# arduino_Uno_ref.net
KiCad netlist of a schematic drawn in EAGLE
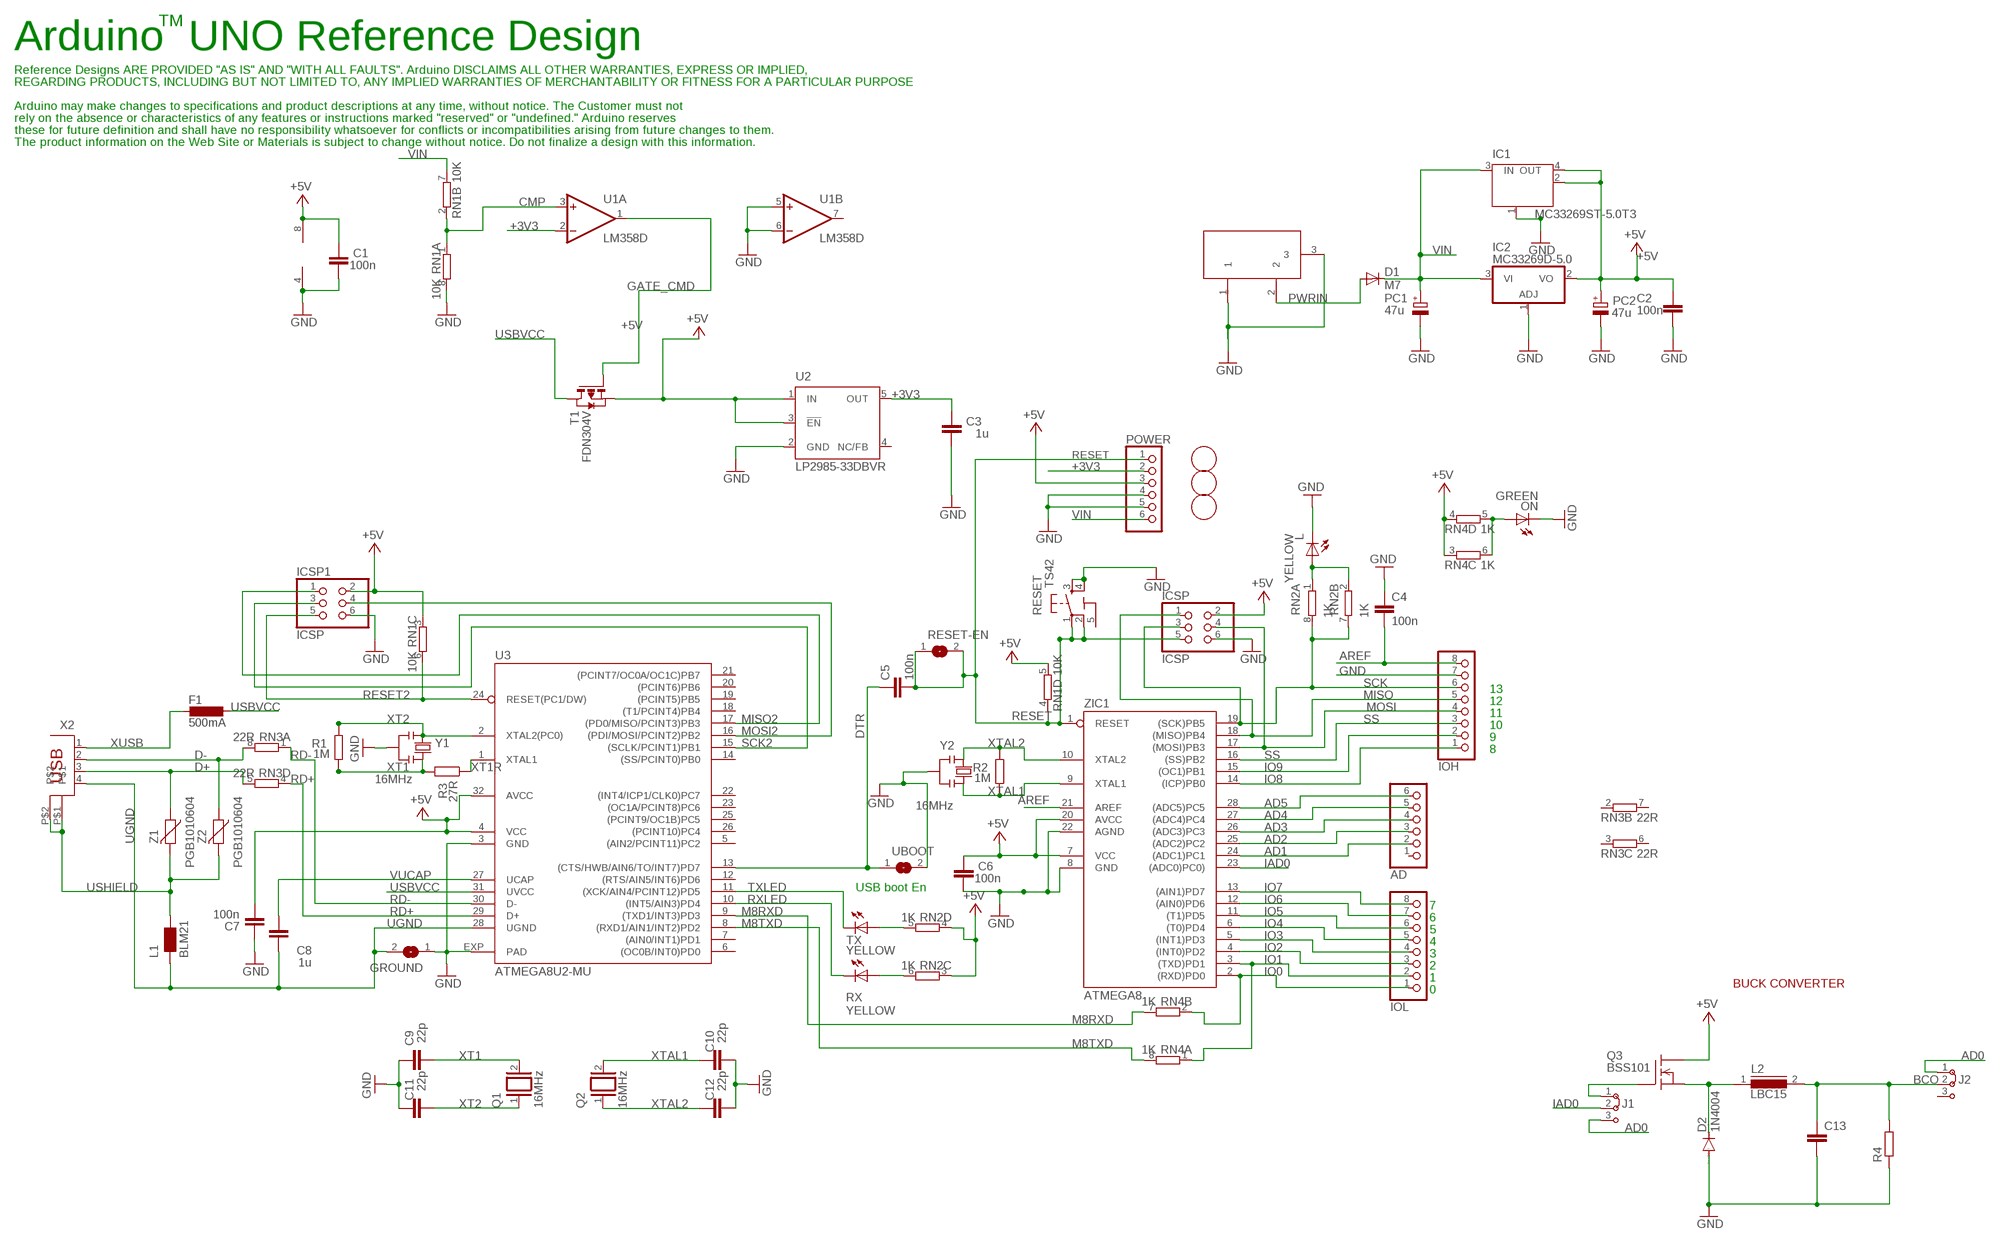
[diagram p0: schematic, sheet 1]

(export (version "E")
  (design (tool "Eeschema 10.0.6"))
  (components
    (comp (ref "AD")
      (value "PINHD-1X6")
      (footprint "eagle-import:1X06")
      (libsource (lib "eagle-import") (part "PINHD-1X6"))
    )
    (comp (ref "C1")
      (value "100n")
      (footprint "eagle-import:C0603-ROUND")
      (libsource (lib "eagle-import") (part "C-EU0603-RND"))
    )
    (comp (ref "C2")
      (value "100n")
      (footprint "eagle-import:C0603-ROUND")
      (libsource (lib "eagle-import") (part "C-EU0603-RND"))
    )
    (comp (ref "C3")
      (value "1u")
      (footprint "eagle-import:C0603-ROUND")
      (libsource (lib "eagle-import") (part "C-EU0603-RND"))
    )
    (comp (ref "C4")
      (value "100n")
      (footprint "eagle-import:C0603-ROUND")
      (libsource (lib "eagle-import") (part "C-EU0603-RND"))
    )
    (comp (ref "C5")
      (value "100n")
      (footprint "eagle-import:C0603-ROUND")
      (libsource (lib "eagle-import") (part "C-EU0603-RND"))
    )
    (comp (ref "C6")
      (value "100n")
      (footprint "eagle-import:C0603-ROUND")
      (libsource (lib "eagle-import") (part "C-EU0603-RND"))
    )
    (comp (ref "C7")
      (value "100n")
      (footprint "eagle-import:C0603-ROUND")
      (libsource (lib "eagle-import") (part "C-EU0603-RND"))
    )
    (comp (ref "C8")
      (value "1u")
      (footprint "eagle-import:C0603-ROUND")
      (libsource (lib "eagle-import") (part "C-EU0603-RND"))
    )
    (comp (ref "C9")
      (value "22p")
      (footprint "eagle-import:C0603-ROUND")
      (libsource (lib "eagle-import") (part "C-EU0603-RND"))
    )
    (comp (ref "C10")
      (value "22p")
      (footprint "eagle-import:C0603-ROUND")
      (libsource (lib "eagle-import") (part "C-EU0603-RND"))
    )
    (comp (ref "C11")
      (value "22p")
      (footprint "eagle-import:C0603-ROUND")
      (libsource (lib "eagle-import") (part "C-EU0603-RND"))
    )
    (comp (ref "C12")
      (value "22p")
      (footprint "eagle-import:C0603-ROUND")
      (libsource (lib "eagle-import") (part "C-EU0603-RND"))
    )
    (comp (ref "C13")
      (value "C2.5/2")
      (footprint "eagle-import:C2.5-2")
      (libsource (lib "eagle-import") (part "C2.5/2"))
    )
    (comp (ref "D1")
      (value "M7")
      (footprint "eagle-import:SMB")
      (libsource (lib "eagle-import") (part "DIODE-SMB"))
    )
    (comp (ref "D2")
      (value "1N4004")
      (footprint "eagle-import:DO41-10")
      (libsource (lib "eagle-import") (part "1N4004"))
    )
    (comp (ref "F1")
      (value "500mA")
      (footprint "eagle-import:L1812")
      (libsource (lib "eagle-import") (part "L-EUL1812"))
    )
    (comp (ref "GROUND")
      (value "SJ")
      (footprint "eagle-import:SJ")
      (libsource (lib "eagle-import") (part "SJ"))
    )
    (comp (ref "IC1")
      (value "MC33269ST-5.0T3")
      (footprint "eagle-import:SOT223")
      (libsource (lib "eagle-import") (part "MC33269ST-3.3T3"))
    )
    (comp (ref "IC2")
      (value "MC33269D-5.0")
      (footprint "eagle-import:DPACK")
      (libsource (lib "eagle-import") (part "MC33269?D-5.0"))
    )
    (comp (ref "ICSP")
      (value "ICSP")
      (footprint "eagle-import:2X03")
      (libsource (lib "eagle-import") (part "PINHD-2X3"))
    )
    (comp (ref "ICSP1")
      (value "ICSP")
      (footprint "eagle-import:2X03")
      (libsource (lib "eagle-import") (part "PINHD-2X3"))
    )
    (comp (ref "IOH")
      (value "PINHD-1X8")
      (footprint "eagle-import:1X08")
      (libsource (lib "eagle-import") (part "PINHD-1X8"))
    )
    (comp (ref "IOL")
      (value "PINHD-1X8")
      (footprint "eagle-import:1X08")
      (libsource (lib "eagle-import") (part "PINHD-1X8"))
    )
    (comp (ref "J1")
      (value "J2X2MM")
      (footprint "eagle-import:04C")
      (libsource (lib "eagle-import") (part "J2X2MM"))
    )
    (comp (ref "J2")
      (value "J2X2MM")
      (footprint "eagle-import:04C")
      (libsource (lib "eagle-import") (part "J2X2MM"))
    )
    (comp (ref "L")
      (value "YELLOW")
      (footprint "eagle-import:CHIP-LED0805")
      (libsource (lib "eagle-import") (part "LEDCHIP-LED0805"))
    )
    (comp (ref "L1")
      (value "BLM21")
      (footprint "eagle-import:0805")
      (libsource (lib "eagle-import") (part "WE-CBF_0805"))
    )
    (comp (ref "L2")
      (value "LBC15")
      (footprint "eagle-import:LBC15")
      (libsource (lib "eagle-import") (part "LBC15"))
    )
    (comp (ref "ON")
      (value "GREEN")
      (footprint "eagle-import:CHIP-LED0805")
      (libsource (lib "eagle-import") (part "LEDCHIP-LED0805"))
    )
    (comp (ref "PC1")
      (value "47u")
      (footprint "eagle-import:PANASONIC_D")
      (libsource (lib "eagle-import") (part "CPOL-EUD"))
    )
    (comp (ref "PC2")
      (value "47u")
      (footprint "eagle-import:PANASONIC_D")
      (libsource (lib "eagle-import") (part "CPOL-EUD"))
    )
    (comp (ref "POWER")
      (value "PINHD-1X6")
      (footprint "eagle-import:1X06")
      (libsource (lib "eagle-import") (part "PINHD-1X6"))
    )
    (comp (ref "Q1")
      (value "16MHz")
      (footprint "eagle-import:QS")
      (libsource (lib "eagle-import") (part "XTAL/S"))
    )
    (comp (ref "Q2")
      (value "16MHz")
      (footprint "eagle-import:QS")
      (libsource (lib "eagle-import") (part "XTAL/S"))
    )
    (comp (ref "Q3")
      (value "BSS101")
      (footprint "eagle-import:TO92")
      (libsource (lib "eagle-import") (part "BSS101"))
    )
    (comp (ref "R1")
      (value "1M")
      (footprint "eagle-import:R0603-ROUND")
      (libsource (lib "eagle-import") (part "R-EU_R0603"))
    )
    (comp (ref "R2")
      (value "1M")
      (footprint "eagle-import:R0603-ROUND")
      (libsource (lib "eagle-import") (part "R-EU_R0603"))
    )
    (comp (ref "R3")
      (value "27R")
      (footprint "eagle-import:R0603-ROUND")
      (libsource (lib "eagle-import") (part "R-EU_R0603"))
    )
    (comp (ref "R4")
      (value "R-EU_0207/10")
      (footprint "eagle-import:0207_10")
      (libsource (lib "eagle-import") (part "rcl_334_R-EU_0207/10"))
    )
    (comp (ref "RESET")
      (value "TS42")
      (footprint "eagle-import:TS42")
      (libsource (lib "eagle-import") (part "TS42"))
    )
    (comp (ref "RESET-EN")
      (value "SJ")
      (footprint "eagle-import:SJ")
      (libsource (lib "eagle-import") (part "SJ"))
    )
    (comp (ref "RN1")
      (value "10K")
      (footprint "eagle-import:CAY16")
      (libsource (lib "eagle-import") (part "4R-NCAY16"))
    )
    (comp (ref "RN2")
      (value "1K")
      (footprint "eagle-import:CAY16")
      (libsource (lib "eagle-import") (part "4R-NCAY16"))
    )
    (comp (ref "RN3")
      (value "22R")
      (footprint "eagle-import:CAY16")
      (libsource (lib "eagle-import") (part "4R-NCAY16"))
    )
    (comp (ref "RN4")
      (value "1K")
      (footprint "eagle-import:CAY16")
      (libsource (lib "eagle-import") (part "4R-NCAY16"))
    )
    (comp (ref "RX")
      (value "YELLOW")
      (footprint "eagle-import:CHIP-LED0805")
      (libsource (lib "eagle-import") (part "LEDCHIP-LED0805"))
    )
    (comp (ref "T1")
      (value "FDN304V")
      (footprint "eagle-import:SOT-23")
      (libsource (lib "eagle-import") (part "PMOSSOT23"))
    )
    (comp (ref "TX")
      (value "YELLOW")
      (footprint "eagle-import:CHIP-LED0805")
      (libsource (lib "eagle-import") (part "LEDCHIP-LED0805"))
    )
    (comp (ref "U$3")
      (value "FIDUCIALMOUNT")
      (footprint "eagle-import:FIDUCIA-MOUNT")
      (libsource (lib "eagle-import") (part "FIDUCIALMOUNT"))
    )
    (comp (ref "U$4")
      (value "FIDUCIALMOUNT")
      (footprint "eagle-import:FIDUCIA-MOUNT")
      (libsource (lib "eagle-import") (part "FIDUCIALMOUNT"))
    )
    (comp (ref "U$6")
      (value "FIDUCIALMOUNT")
      (footprint "eagle-import:FIDUCIA-MOUNT")
      (libsource (lib "eagle-import") (part "FIDUCIALMOUNT"))
    )
    (comp (ref "U1")
      (value "LM358D")
      (footprint "eagle-import:SO08")
      (libsource (lib "eagle-import") (part "LM358D"))
    )
    (comp (ref "U2")
      (value "LP2985-33DBVR")
      (footprint "eagle-import:SOT23-DBV")
      (libsource (lib "eagle-import") (part "TPS77033"))
    )
    (comp (ref "U3")
      (value "ATMEGA8U2-MU")
      (footprint "eagle-import:QFN32")
      (libsource (lib "eagle-import") (part "ATMEGA8U2-MU"))
    )
    (comp (ref "UBOOT")
      (value "SJ")
      (footprint "eagle-import:SJ")
      (libsource (lib "eagle-import") (part "SJ"))
    )
    (comp (ref "X1")
      (value "DC21MMX")
      (footprint "eagle-import:DC-21MM")
      (libsource (lib "eagle-import") (part "DC21MMX"))
    )
    (comp (ref "X2")
      (value "PN61729")
      (footprint "eagle-import:PN61729")
      (libsource (lib "eagle-import") (part "PN61729"))
    )
    (comp (ref "Y1")
      (value "16MHz")
      (footprint "eagle-import:RESONATOR")
      (libsource (lib "eagle-import") (part "RESONATORMU"))
    )
    (comp (ref "Y2")
      (value "16MHz")
      (footprint "eagle-import:RESONATOR")
      (libsource (lib "eagle-import") (part "RESONATORMU"))
    )
    (comp (ref "Z1")
      (value "PGB1010604")
      (footprint "eagle-import:CT_CN0603")
      (libsource (lib "eagle-import") (part "VARISTORCN0603"))
    )
    (comp (ref "Z2")
      (value "PGB1010604")
      (footprint "eagle-import:CT_CN0603")
      (libsource (lib "eagle-import") (part "VARISTORCN0603"))
    )
    (comp (ref "ZIC1")
      (value "ATMEGA8")
      (footprint "eagle-import:DIL28-3")
      (libsource (lib "eagle-import") (part "AT90S4433P"))
    )
  )
  (nets
    (net (code "1") (name "+5V") (class "Default")
      (node (ref "C1") (pin "2") (pinfunction "2_2") (pintype "passive"))
      (node (ref "C2") (pin "2") (pinfunction "2_2") (pintype "passive"))
      (node (ref "C6") (pin "2") (pinfunction "2_2") (pintype "passive"))
      (node (ref "C7") (pin "1") (pinfunction "1_1") (pintype "passive"))
      (node (ref "IC1") (pin "2") (pinfunction "OUT_2") (pintype "passive"))
      (node (ref "IC1") (pin "4") (pinfunction "OUT_4") (pintype "passive"))
      (node (ref "IC2") (pin "2") (pinfunction "VO_2") (pintype "passive"))
      (node (ref "ICSP") (pin "2") (pinfunction "2_2") (pintype "passive"))
      (node (ref "ICSP1") (pin "2") (pinfunction "2_2") (pintype "passive"))
      (node (ref "PC2") (pin "+") (pinfunction "+_+") (pintype "passive"))
      (node (ref "POWER") (pin "3") (pinfunction "3_3") (pintype "passive"))
      (node (ref "Q3") (pin "3") (pinfunction "D_3") (pintype "passive"))
      (node (ref "RN1") (pin "3") (pinfunction "1_3") (pintype "passive"))
      (node (ref "RN1") (pin "5") (pinfunction "2_5") (pintype "passive"))
      (node (ref "RN2") (pin "3") (pinfunction "1_3") (pintype "passive"))
      (node (ref "RN2") (pin "4") (pinfunction "1_4") (pintype "passive"))
      (node (ref "RN4") (pin "3") (pinfunction "1_3") (pintype "passive"))
      (node (ref "RN4") (pin "4") (pinfunction "1_4") (pintype "passive"))
      (node (ref "T1") (pin "2") (pinfunction "S_2") (pintype "passive"))
      (node (ref "U1") (pin "8") (pinfunction "V+_8") (pintype "power_in"))
      (node (ref "U2") (pin "1") (pinfunction "IN_1") (pintype "input"))
      (node (ref "U2") (pin "3") (pinfunction "~{EN}_3") (pintype "input"))
      (node (ref "U3") (pin "32") (pinfunction "AVCC_32") (pintype "power_in"))
      (node (ref "U3") (pin "4") (pinfunction "VCC_4") (pintype "power_in"))
      (node (ref "ZIC1") (pin "20") (pinfunction "AVCC_20") (pintype "power_in"))
      (node (ref "ZIC1") (pin "7") (pinfunction "VCC_7") (pintype "power_in"))
    )
    (net (code "2") (name "/+3V3") (class "Default")
      (node (ref "C3") (pin "2") (pinfunction "2_2") (pintype "passive"))
      (node (ref "POWER") (pin "2") (pinfunction "2_2") (pintype "passive"))
      (node (ref "U1") (pin "2") (pinfunction "-IN_2") (pintype "input"))
      (node (ref "U2") (pin "5") (pinfunction "OUT_5") (pintype "passive"))
    )
    (net (code "3") (name "/5-GND") (class "Default")
      (node (ref "RESET") (pin "5") (pinfunction "5-GND_5") (pintype "power_in"))
    )
    (net (code "4") (name "/AD0") (class "Default")
      (node (ref "J1") (pin "3") (pinfunction "3_3") (pintype "passive"))
      (node (ref "J2") (pin "1") (pinfunction "1_1") (pintype "passive"))
    )
    (net (code "5") (name "/AD1") (class "Default")
      (node (ref "AD") (pin "2") (pinfunction "2_2") (pintype "passive"))
      (node (ref "ZIC1") (pin "24") (pinfunction "(ADC1)PC1_24") (pintype "bidirectional"))
    )
    (net (code "6") (name "/AD2") (class "Default")
      (node (ref "AD") (pin "3") (pinfunction "3_3") (pintype "passive"))
      (node (ref "ZIC1") (pin "25") (pinfunction "(ADC2)PC2_25") (pintype "bidirectional"))
    )
    (net (code "7") (name "/AD3") (class "Default")
      (node (ref "AD") (pin "4") (pinfunction "4_4") (pintype "passive"))
      (node (ref "ZIC1") (pin "26") (pinfunction "(ADC3)PC3_26") (pintype "bidirectional"))
    )
    (net (code "8") (name "/AD4") (class "Default")
      (node (ref "AD") (pin "5") (pinfunction "5_5") (pintype "passive"))
      (node (ref "ZIC1") (pin "27") (pinfunction "(ADC4)PC4_27") (pintype "bidirectional"))
    )
    (net (code "9") (name "/AD5") (class "Default")
      (node (ref "AD") (pin "6") (pinfunction "6_6") (pintype "passive"))
      (node (ref "ZIC1") (pin "28") (pinfunction "(ADC5)PC5_28") (pintype "bidirectional"))
    )
    (net (code "10") (name "/AREF") (class "Default")
      (node (ref "C4") (pin "2") (pinfunction "2_2") (pintype "passive"))
      (node (ref "IOH") (pin "8") (pinfunction "8_8") (pintype "passive"))
      (node (ref "ZIC1") (pin "21") (pinfunction "AREF_21") (pintype "passive"))
    )
    (net (code "11") (name "/BCO") (class "Default")
      (node (ref "C13") (pin "1") (pinfunction "1_1") (pintype "passive"))
      (node (ref "J2") (pin "2") (pinfunction "2_2") (pintype "passive"))
      (node (ref "L2") (pin "2") (pinfunction "2_2") (pintype "passive"))
      (node (ref "R4") (pin "2") (pinfunction "2_2") (pintype "passive"))
    )
    (net (code "12") (name "/CMP") (class "Default")
      (node (ref "RN1") (pin "1") (pinfunction "1_1") (pintype "passive"))
      (node (ref "RN1") (pin "2") (pinfunction "1_2") (pintype "passive"))
      (node (ref "U1") (pin "3") (pinfunction "+IN_3") (pintype "input"))
    )
    (net (code "13") (name "/D+") (class "Default")
      (node (ref "RN3") (pin "5") (pinfunction "2_5") (pintype "passive"))
      (node (ref "X2") (pin "3") (pinfunction "3_3") (pintype "bidirectional"))
      (node (ref "Z1") (pin "1") (pinfunction "1_1") (pintype "passive"))
    )
    (net (code "14") (name "/D-") (class "Default")
      (node (ref "RN3") (pin "8") (pinfunction "2_8") (pintype "passive"))
      (node (ref "X2") (pin "2") (pinfunction "2_2") (pintype "bidirectional"))
      (node (ref "Z2") (pin "1") (pinfunction "1_1") (pintype "passive"))
    )
    (net (code "15") (name "/DTR") (class "Default")
      (node (ref "C5") (pin "1") (pinfunction "1_1") (pintype "passive"))
      (node (ref "U3") (pin "13") (pinfunction "(CTS/HWB/AIN6/TO/INT7)PD7_13") (pintype "bidirectional"))
      (node (ref "UBOOT") (pin "1") (pinfunction "1_1") (pintype "passive"))
    )
    (net (code "16") (name "/GATE_CMD") (class "Default")
      (node (ref "T1") (pin "3") (pinfunction "G_3") (pintype "passive"))
      (node (ref "U1") (pin "1") (pinfunction "OUT_1") (pintype "output"))
    )
    (net (code "17") (name "/IAD0") (class "Default")
      (node (ref "J1") (pin "2") (pinfunction "2_2") (pintype "passive"))
      (node (ref "ZIC1") (pin "23") (pinfunction "(ADC0)PC0)_23") (pintype "bidirectional"))
    )
    (net (code "18") (name "/IO0") (class "Default")
      (node (ref "IOL") (pin "1") (pinfunction "1_1") (pintype "passive"))
      (node (ref "RN4") (pin "2") (pinfunction "1_2") (pintype "passive"))
      (node (ref "ZIC1") (pin "2") (pinfunction "(RXD)PD0_2") (pintype "bidirectional"))
    )
    (net (code "19") (name "/IO1") (class "Default")
      (node (ref "IOL") (pin "2") (pinfunction "2_2") (pintype "passive"))
      (node (ref "RN4") (pin "1") (pinfunction "1_1") (pintype "passive"))
      (node (ref "ZIC1") (pin "3") (pinfunction "(TXD)PD1_3") (pintype "bidirectional"))
    )
    (net (code "20") (name "/IO2") (class "Default")
      (node (ref "IOL") (pin "3") (pinfunction "3_3") (pintype "passive"))
      (node (ref "ZIC1") (pin "4") (pinfunction "(INT0)PD2_4") (pintype "bidirectional"))
    )
    (net (code "21") (name "/IO3") (class "Default")
      (node (ref "IOL") (pin "4") (pinfunction "4_4") (pintype "passive"))
      (node (ref "ZIC1") (pin "5") (pinfunction "(INT1)PD3_5") (pintype "bidirectional"))
    )
    (net (code "22") (name "/IO4") (class "Default")
      (node (ref "IOL") (pin "5") (pinfunction "5_5") (pintype "passive"))
      (node (ref "ZIC1") (pin "6") (pinfunction "(T0)PD4_6") (pintype "bidirectional"))
    )
    (net (code "23") (name "/IO5") (class "Default")
      (node (ref "IOL") (pin "6") (pinfunction "6_6") (pintype "passive"))
      (node (ref "ZIC1") (pin "11") (pinfunction "(T1)PD5_11") (pintype "bidirectional"))
    )
    (net (code "24") (name "/IO6") (class "Default")
      (node (ref "IOL") (pin "7") (pinfunction "7_7") (pintype "passive"))
      (node (ref "ZIC1") (pin "12") (pinfunction "(AIN0)PD6_12") (pintype "bidirectional"))
    )
    (net (code "25") (name "/IO7") (class "Default")
      (node (ref "IOL") (pin "8") (pinfunction "8_8") (pintype "passive"))
      (node (ref "ZIC1") (pin "13") (pinfunction "(AIN1)PD7_13") (pintype "bidirectional"))
    )
    (net (code "26") (name "/IO8") (class "Default")
      (node (ref "IOH") (pin "1") (pinfunction "1_1") (pintype "passive"))
      (node (ref "ZIC1") (pin "14") (pinfunction "(ICP)PB0_14") (pintype "bidirectional"))
    )
    (net (code "27") (name "/IO9") (class "Default")
      (node (ref "IOH") (pin "2") (pinfunction "2_2") (pintype "passive"))
      (node (ref "ZIC1") (pin "15") (pinfunction "(OC1)PB1_15") (pintype "bidirectional"))
    )
    (net (code "28") (name "/M8RXD") (class "Default")
      (node (ref "RN4") (pin "7") (pinfunction "2_7") (pintype "passive"))
      (node (ref "U3") (pin "9") (pinfunction "(TXD1/INT3)PD3_9") (pintype "bidirectional"))
    )
    (net (code "29") (name "/M8TXD") (class "Default")
      (node (ref "RN4") (pin "8") (pinfunction "2_8") (pintype "passive"))
      (node (ref "U3") (pin "8") (pinfunction "(RXD1/AIN1/INT2)PD2_8") (pintype "bidirectional"))
    )
    (net (code "30") (name "/MISO") (class "Default")
      (node (ref "ICSP") (pin "1") (pinfunction "1_1") (pintype "passive"))
      (node (ref "IOH") (pin "5") (pinfunction "5_5") (pintype "passive"))
      (node (ref "ZIC1") (pin "18") (pinfunction "(MISO)PB4_18") (pintype "bidirectional"))
    )
    (net (code "31") (name "/MISO2") (class "Default")
      (node (ref "ICSP1") (pin "1") (pinfunction "1_1") (pintype "passive"))
      (node (ref "U3") (pin "17") (pinfunction "(PD0/MISO/PCINT3)PB3_17") (pintype "bidirectional"))
    )
    (net (code "32") (name "/MOSI") (class "Default")
      (node (ref "ICSP") (pin "4") (pinfunction "4_4") (pintype "passive"))
      (node (ref "IOH") (pin "4") (pinfunction "4_4") (pintype "passive"))
      (node (ref "ZIC1") (pin "17") (pinfunction "(MOSI)PB3_17") (pintype "bidirectional"))
    )
    (net (code "33") (name "/MOSI2") (class "Default")
      (node (ref "ICSP1") (pin "4") (pinfunction "4_4") (pintype "passive"))
      (node (ref "U3") (pin "16") (pinfunction "(PDI/MOSI/PCINT2)PB2_16") (pintype "bidirectional"))
    )
    (net (code "34") (name "/PWRIN") (class "Default")
      (node (ref "D1") (pin "A") (pinfunction "A_A") (pintype "passive"))
      (node (ref "X1") (pin "2") (pinfunction "2_2") (pintype "power_in"))
    )
    (net (code "35") (name "/RD+") (class "Default")
      (node (ref "RN3") (pin "4") (pinfunction "1_4") (pintype "passive"))
      (node (ref "U3") (pin "29") (pinfunction "D+_29") (pintype "bidirectional"))
    )
    (net (code "36") (name "/RD-") (class "Default")
      (node (ref "RN3") (pin "1") (pinfunction "1_1") (pintype "passive"))
      (node (ref "U3") (pin "30") (pinfunction "D-_30") (pintype "bidirectional"))
    )
    (net (code "37") (name "/RESET") (class "Default")
      (node (ref "C5") (pin "2") (pinfunction "2_2") (pintype "passive"))
      (node (ref "ICSP") (pin "5") (pinfunction "5_5") (pintype "passive"))
      (node (ref "POWER") (pin "1") (pinfunction "1_1") (pintype "passive"))
      (node (ref "RESET") (pin "1") (pinfunction "1_1") (pintype "passive"))
      (node (ref "RESET") (pin "2") (pinfunction "2_2") (pintype "passive"))
      (node (ref "RESET-EN") (pin "1") (pinfunction "1_1") (pintype "passive"))
      (node (ref "RESET-EN") (pin "2") (pinfunction "2_2") (pintype "passive"))
      (node (ref "RN1") (pin "4") (pinfunction "1_4") (pintype "passive"))
      (node (ref "ZIC1") (pin "1") (pinfunction "RESET_1") (pintype "input"))
    )
    (net (code "38") (name "/RESET2") (class "Default")
      (node (ref "ICSP1") (pin "5") (pinfunction "5_5") (pintype "passive"))
      (node (ref "RN1") (pin "6") (pinfunction "2_6") (pintype "passive"))
      (node (ref "U3") (pin "24") (pinfunction "RESET(PC1/DW)_24") (pintype "input"))
    )
    (net (code "39") (name "/RXLED") (class "Default")
      (node (ref "RX") (pin "C") (pinfunction "C_C") (pintype "passive"))
      (node (ref "U3") (pin "10") (pinfunction "(INT5/AIN3)PD4_10") (pintype "bidirectional"))
    )
    (net (code "40") (name "/SCK") (class "Default")
      (node (ref "ICSP") (pin "3") (pinfunction "3_3") (pintype "passive"))
      (node (ref "IOH") (pin "6") (pinfunction "6_6") (pintype "passive"))
      (node (ref "RN2") (pin "7") (pinfunction "2_7") (pintype "passive"))
      (node (ref "RN2") (pin "8") (pinfunction "2_8") (pintype "passive"))
      (node (ref "ZIC1") (pin "19") (pinfunction "(SCK)PB5_19") (pintype "bidirectional"))
    )
    (net (code "41") (name "/SCK2") (class "Default")
      (node (ref "ICSP1") (pin "3") (pinfunction "3_3") (pintype "passive"))
      (node (ref "U3") (pin "15") (pinfunction "(SCLK/PCINT1)PB1_15") (pintype "bidirectional"))
    )
    (net (code "42") (name "/SS") (class "Default")
      (node (ref "IOH") (pin "3") (pinfunction "3_3") (pintype "passive"))
      (node (ref "ZIC1") (pin "16") (pinfunction "(SS)PB2_16") (pintype "bidirectional"))
    )
    (net (code "43") (name "/TXLED") (class "Default")
      (node (ref "TX") (pin "C") (pinfunction "C_C") (pintype "passive"))
      (node (ref "U3") (pin "11") (pinfunction "(XCK/AIN4/PCINT12)PD5_11") (pintype "bidirectional"))
    )
    (net (code "44") (name "/UGND") (class "Default")
      (node (ref "C8") (pin "2") (pinfunction "2_2") (pintype "passive"))
      (node (ref "GROUND") (pin "2") (pinfunction "2_2") (pintype "passive"))
      (node (ref "L1") (pin "1") (pinfunction "1_1") (pintype "passive"))
      (node (ref "U3") (pin "28") (pinfunction "UGND_28") (pintype "power_in"))
      (node (ref "X2") (pin "4") (pinfunction "4_4") (pintype "bidirectional"))
    )
    (net (code "45") (name "/USBVCC") (class "Default")
      (node (ref "F1") (pin "1") (pinfunction "1_1") (pintype "passive"))
      (node (ref "T1") (pin "1") (pinfunction "D_1") (pintype "passive"))
      (node (ref "U3") (pin "31") (pinfunction "UVCC_31") (pintype "power_in"))
    )
    (net (code "46") (name "/USHIELD") (class "Default")
      (node (ref "L1") (pin "2") (pinfunction "2_2") (pintype "passive"))
      (node (ref "X2") (pin "P$1") (pinfunction "P$1_P$1") (pintype "bidirectional"))
      (node (ref "X2") (pin "P$2") (pinfunction "P$2_P$2") (pintype "bidirectional"))
      (node (ref "Z1") (pin "2") (pinfunction "2_2") (pintype "passive"))
      (node (ref "Z2") (pin "2") (pinfunction "2_2") (pintype "passive"))
    )
    (net (code "47") (name "/VIN") (class "Default")
      (node (ref "D1") (pin "C") (pinfunction "C_C") (pintype "passive"))
      (node (ref "IC1") (pin "3") (pinfunction "IN_3") (pintype "input"))
      (node (ref "IC2") (pin "3") (pinfunction "VI_3") (pintype "input"))
      (node (ref "PC1") (pin "+") (pinfunction "+_+") (pintype "passive"))
      (node (ref "POWER") (pin "6") (pinfunction "6_6") (pintype "passive"))
      (node (ref "RN1") (pin "7") (pinfunction "2_7") (pintype "passive"))
    )
    (net (code "48") (name "/VUCAP") (class "Default")
      (node (ref "C8") (pin "1") (pinfunction "1_1") (pintype "passive"))
      (node (ref "U3") (pin "27") (pinfunction "UCAP_27") (pintype "passive"))
    )
    (net (code "49") (name "/XT1") (class "Default")
      (node (ref "C9") (pin "1") (pinfunction "1_1") (pintype "passive"))
      (node (ref "Q1") (pin "2") (pinfunction "2_2") (pintype "passive"))
      (node (ref "R1") (pin "1") (pinfunction "1_1") (pintype "passive"))
      (node (ref "R3") (pin "2") (pinfunction "2_2") (pintype "passive"))
      (node (ref "Y1") (pin "3") (pinfunction "3_3") (pintype "passive"))
    )
    (net (code "50") (name "/XT1R") (class "Default")
      (node (ref "R3") (pin "1") (pinfunction "1_1") (pintype "passive"))
      (node (ref "U3") (pin "1") (pinfunction "XTAL1_1") (pintype "bidirectional"))
    )
    (net (code "51") (name "/XT2") (class "Default")
      (node (ref "C11") (pin "1") (pinfunction "1_1") (pintype "passive"))
      (node (ref "Q1") (pin "1") (pinfunction "1_1") (pintype "passive"))
      (node (ref "R1") (pin "2") (pinfunction "2_2") (pintype "passive"))
      (node (ref "U3") (pin "2") (pinfunction "XTAL2(PC0)_2") (pintype "bidirectional"))
      (node (ref "Y1") (pin "1") (pinfunction "1_1") (pintype "passive"))
    )
    (net (code "52") (name "/XTAL1") (class "Default")
      (node (ref "C10") (pin "2") (pinfunction "2_2") (pintype "passive"))
      (node (ref "Q2") (pin "2") (pinfunction "2_2") (pintype "passive"))
      (node (ref "R2") (pin "1") (pinfunction "1_1") (pintype "passive"))
      (node (ref "Y2") (pin "3") (pinfunction "3_3") (pintype "passive"))
      (node (ref "ZIC1") (pin "9") (pinfunction "XTAL1_9") (pintype "bidirectional"))
    )
    (net (code "53") (name "/XTAL2") (class "Default")
      (node (ref "C12") (pin "2") (pinfunction "2_2") (pintype "passive"))
      (node (ref "Q2") (pin "1") (pinfunction "1_1") (pintype "passive"))
      (node (ref "R2") (pin "2") (pinfunction "2_2") (pintype "passive"))
      (node (ref "Y2") (pin "1") (pinfunction "1_1") (pintype "passive"))
      (node (ref "ZIC1") (pin "10") (pinfunction "XTAL2_10") (pintype "bidirectional"))
    )
    (net (code "54") (name "/XUSB") (class "Default")
      (node (ref "F1") (pin "2") (pinfunction "2_2") (pintype "passive"))
      (node (ref "X2") (pin "1") (pinfunction "1_1") (pintype "bidirectional"))
    )
    (net (code "55") (name "GND") (class "Default")
      (node (ref "C1") (pin "1") (pinfunction "1_1") (pintype "passive"))
      (node (ref "C10") (pin "1") (pinfunction "1_1") (pintype "passive"))
      (node (ref "C11") (pin "2") (pinfunction "2_2") (pintype "passive"))
      (node (ref "C12") (pin "1") (pinfunction "1_1") (pintype "passive"))
      (node (ref "C13") (pin "2") (pinfunction "2_2") (pintype "passive"))
      (node (ref "C2") (pin "1") (pinfunction "1_1") (pintype "passive"))
      (node (ref "C3") (pin "1") (pinfunction "1_1") (pintype "passive"))
      (node (ref "C4") (pin "1") (pinfunction "1_1") (pintype "passive"))
      (node (ref "C6") (pin "1") (pinfunction "1_1") (pintype "passive"))
      (node (ref "C7") (pin "2") (pinfunction "2_2") (pintype "passive"))
      (node (ref "C9") (pin "2") (pinfunction "2_2") (pintype "passive"))
      (node (ref "D2") (pin "A") (pinfunction "A_A") (pintype "passive"))
      (node (ref "GROUND") (pin "1") (pinfunction "1_1") (pintype "passive"))
      (node (ref "IC1") (pin "1") (pinfunction "GND/ADJ_1") (pintype "input"))
      (node (ref "IC2") (pin "1") (pinfunction "ADJ_1") (pintype "input"))
      (node (ref "ICSP") (pin "6") (pinfunction "6_6") (pintype "passive"))
      (node (ref "ICSP1") (pin "6") (pinfunction "6_6") (pintype "passive"))
      (node (ref "IOH") (pin "7") (pinfunction "7_7") (pintype "passive"))
      (node (ref "L") (pin "C") (pinfunction "C_C") (pintype "passive"))
      (node (ref "ON") (pin "C") (pinfunction "C_C") (pintype "passive"))
      (node (ref "PC1") (pin "-") (pinfunction "-_-") (pintype "passive"))
      (node (ref "PC2") (pin "-") (pinfunction "-_-") (pintype "passive"))
      (node (ref "POWER") (pin "4") (pinfunction "4_4") (pintype "passive"))
      (node (ref "POWER") (pin "5") (pinfunction "5_5") (pintype "passive"))
      (node (ref "R4") (pin "1") (pinfunction "1_1") (pintype "passive"))
      (node (ref "RESET") (pin "3") (pinfunction "3_3") (pintype "passive"))
      (node (ref "RESET") (pin "4") (pinfunction "4_4") (pintype "passive"))
      (node (ref "RN1") (pin "8") (pinfunction "2_8") (pintype "passive"))
      (node (ref "U1") (pin "4") (pinfunction "V-_4") (pintype "power_in"))
      (node (ref "U1") (pin "5") (pinfunction "+IN_5") (pintype "input"))
      (node (ref "U1") (pin "6") (pinfunction "-IN_6") (pintype "input"))
      (node (ref "U2") (pin "2") (pinfunction "GND_2") (pintype "power_in"))
      (node (ref "U3") (pin "3") (pinfunction "GND_3") (pintype "power_in"))
      (node (ref "U3") (pin "EXP") (pinfunction "PAD_EXP") (pintype "power_in"))
      (node (ref "UBOOT") (pin "2") (pinfunction "2_2") (pintype "passive"))
      (node (ref "X1") (pin "1") (pinfunction "1_1") (pintype "power_in"))
      (node (ref "X1") (pin "3") (pinfunction "3_3") (pintype "power_in"))
      (node (ref "Y1") (pin "2") (pinfunction "2_2") (pintype "passive"))
      (node (ref "Y2") (pin "2") (pinfunction "2_2") (pintype "passive"))
      (node (ref "ZIC1") (pin "22") (pinfunction "AGND_22") (pintype "power_in"))
      (node (ref "ZIC1") (pin "8") (pinfunction "GND_8") (pintype "power_in"))
    )
    (net (code "56") (name "Net-(Q3-G)") (class "Default")
      (node (ref "J1") (pin "1") (pinfunction "1_1") (pintype "passive"))
      (node (ref "Q3") (pin "2") (pinfunction "G_2") (pintype "passive"))
    )
    (net (code "57") (name "Net-(Q3-S)") (class "Default")
      (node (ref "D2") (pin "C") (pinfunction "C_C") (pintype "passive"))
      (node (ref "L2") (pin "1") (pinfunction "1_1") (pintype "passive"))
      (node (ref "Q3") (pin "1") (pinfunction "S_1") (pintype "passive"))
    )
    (net (code "58") (name "Net-(RN2B-1)") (class "Default")
      (node (ref "L") (pin "A") (pinfunction "A_A") (pintype "passive"))
      (node (ref "RN2") (pin "1") (pinfunction "1_1") (pintype "passive"))
      (node (ref "RN2") (pin "2") (pinfunction "1_2") (pintype "passive"))
    )
    (net (code "59") (name "Net-(RN2C-2)") (class "Default")
      (node (ref "RN2") (pin "6") (pinfunction "2_6") (pintype "passive"))
      (node (ref "RX") (pin "A") (pinfunction "A_A") (pintype "passive"))
    )
    (net (code "60") (name "Net-(RN2D-2)") (class "Default")
      (node (ref "RN2") (pin "5") (pinfunction "2_5") (pintype "passive"))
      (node (ref "TX") (pin "A") (pinfunction "A_A") (pintype "passive"))
    )
    (net (code "61") (name "Net-(RN4C-2)") (class "Default")
      (node (ref "ON") (pin "A") (pinfunction "A_A") (pintype "passive"))
      (node (ref "RN4") (pin "5") (pinfunction "2_5") (pintype "passive"))
      (node (ref "RN4") (pin "6") (pinfunction "2_6") (pintype "passive"))
    )
    (net (code "62") (name "unconnected-(AD-Pad1)") (class "Default")
      (node (ref "AD") (pin "1") (pinfunction "1_1") (pintype "passive"))
    )
    (net (code "63") (name "unconnected-(J2-Pad3)") (class "Default")
      (node (ref "J2") (pin "3") (pinfunction "3_3") (pintype "passive"))
    )
    (net (code "64") (name "unconnected-(RN3B-1-Pad2)") (class "Default")
      (node (ref "RN3") (pin "2") (pinfunction "1_2") (pintype "passive"))
    )
    (net (code "65") (name "unconnected-(RN3B-2-Pad7)") (class "Default")
      (node (ref "RN3") (pin "7") (pinfunction "2_7") (pintype "passive"))
    )
    (net (code "66") (name "unconnected-(RN3C-1-Pad3)") (class "Default")
      (node (ref "RN3") (pin "3") (pinfunction "1_3") (pintype "passive"))
    )
    (net (code "67") (name "unconnected-(RN3C-2-Pad6)") (class "Default")
      (node (ref "RN3") (pin "6") (pinfunction "2_6") (pintype "passive"))
    )
    (net (code "68") (name "unconnected-(U1B-OUT-Pad7)") (class "Default")
      (node (ref "U1") (pin "7") (pinfunction "OUT_7") (pintype "output"))
    )
    (net (code "69") (name "unconnected-(U2-NC{slash}FB-Pad4)") (class "Default")
      (node (ref "U2") (pin "4") (pinfunction "NC/FB_4") (pintype "passive"))
    )
    (net (code "70") (name "unconnected-(U3-(AIN0{slash}INT1)PD1-Pad7)") (class "Default")
      (node (ref "U3") (pin "7") (pinfunction "(AIN0/INT1)PD1_7") (pintype "bidirectional"))
    )
    (net (code "71") (name "unconnected-(U3-(AIN2{slash}PCINT11)PC2-Pad5)") (class "Default")
      (node (ref "U3") (pin "5") (pinfunction "(AIN2/PCINT11)PC2_5") (pintype "bidirectional"))
    )
    (net (code "72") (name "unconnected-(U3-(INT4{slash}ICP1{slash}CLK0)PC7-Pad22)") (class "Default")
      (node (ref "U3") (pin "22") (pinfunction "(INT4/ICP1/CLK0)PC7_22") (pintype "bidirectional"))
    )
    (net (code "73") (name "unconnected-(U3-(OC0B{slash}INT0)PD0-Pad6)") (class "Default")
      (node (ref "U3") (pin "6") (pinfunction "(OC0B/INT0)PD0_6") (pintype "bidirectional"))
    )
    (net (code "74") (name "unconnected-(U3-(OC1A{slash}PCINT8)PC6-Pad23)") (class "Default")
      (node (ref "U3") (pin "23") (pinfunction "(OC1A/PCINT8)PC6_23") (pintype "bidirectional"))
    )
    (net (code "75") (name "unconnected-(U3-(PCINT5)PB5-Pad19)") (class "Default")
      (node (ref "U3") (pin "19") (pinfunction "(PCINT5)PB5_19") (pintype "bidirectional"))
    )
    (net (code "76") (name "unconnected-(U3-(PCINT6)PB6-Pad20)") (class "Default")
      (node (ref "U3") (pin "20") (pinfunction "(PCINT6)PB6_20") (pintype "bidirectional"))
    )
    (net (code "77") (name "unconnected-(U3-(PCINT7{slash}OC0A{slash}OC1C)PB7-Pad21)") (class "Default")
      (node (ref "U3") (pin "21") (pinfunction "(PCINT7/OC0A/OC1C)PB7_21") (pintype "bidirectional"))
    )
    (net (code "78") (name "unconnected-(U3-(PCINT9{slash}OC1B)PC5-Pad25)") (class "Default")
      (node (ref "U3") (pin "25") (pinfunction "(PCINT9/OC1B)PC5_25") (pintype "bidirectional"))
    )
    (net (code "79") (name "unconnected-(U3-(PCINT10)PC4-Pad26)") (class "Default")
      (node (ref "U3") (pin "26") (pinfunction "(PCINT10)PC4_26") (pintype "bidirectional"))
    )
    (net (code "80") (name "unconnected-(U3-(RTS{slash}AIN5{slash}INT6)PD6-Pad12)") (class "Default")
      (node (ref "U3") (pin "12") (pinfunction "(RTS/AIN5/INT6)PD6_12") (pintype "bidirectional"))
    )
    (net (code "81") (name "unconnected-(U3-(SS{slash}PCINT0)PB0-Pad14)") (class "Default")
      (node (ref "U3") (pin "14") (pinfunction "(SS/PCINT0)PB0_14") (pintype "bidirectional"))
    )
    (net (code "82") (name "unconnected-(U3-(T1{slash}PCINT4)PB4-Pad18)") (class "Default")
      (node (ref "U3") (pin "18") (pinfunction "(T1/PCINT4)PB4_18") (pintype "bidirectional"))
    )
  )
)
